# passive_volume_control.net
KiCad netlist of a schematic drawn in EAGLE
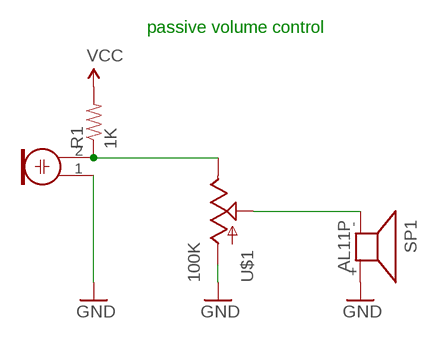
[diagram p0: schematic, sheet 1]

(export (version "E")
  (design (tool "Eeschema 10.0.6"))
  (components
    (comp (ref "M1")
      (value "ELECTRET_MICROPHON-F6035AP")
      (footprint "eagle-import:F6035AP")
      (libsource (lib "eagle-import") (part "ELECTRET_MICROPHON-F6035AP"))
    )
    (comp (ref "R1")
      (value "1K")
      (footprint "eagle-import:AXIAL-0.3")
      (libsource (lib "eagle-import") (part "RESISTORAXIAL-0.3"))
    )
    (comp (ref "SP1")
      (value "AL11P")
      (footprint "eagle-import:AL11P")
      (libsource (lib "eagle-import") (part "AL11P"))
    )
    (comp (ref "U$1")
      (value "100K")
      (footprint "eagle-import:ALPS_POT")
      (libsource (lib "eagle-import") (part "POT"))
    )
  )
  (nets
    (net (code "1") (name "GND") (class "Default")
      (node (ref "M1") (pin "1") (pinfunction "1_1") (pintype "passive"))
      (node (ref "SP1") (pin "+") (pinfunction "2_+") (pintype "passive"))
      (node (ref "U$1") (pin "P$3") (pinfunction "A_P$3") (pintype "passive"))
    )
    (net (code "2") (name "Net-(R1-1)") (class "Default")
      (node (ref "M1") (pin "2") (pinfunction "2_2") (pintype "passive"))
      (node (ref "R1") (pin "P$1") (pinfunction "1_P$1") (pintype "passive"))
      (node (ref "U$1") (pin "P$1") (pinfunction "E_P$1") (pintype "passive"))
    )
    (net (code "3") (name "Net-(SP1-1)") (class "Default")
      (node (ref "SP1") (pin "-") (pinfunction "1_-") (pintype "passive"))
      (node (ref "U$1") (pin "P$2") (pinfunction "S_P$2") (pintype "passive"))
    )
    (net (code "4") (name "VCC") (class "Default")
      (node (ref "R1") (pin "P$2") (pinfunction "2_P$2") (pintype "passive"))
    )
  )
)
